# 18.net
KiCad netlist of a schematic drawn in Altium Designer
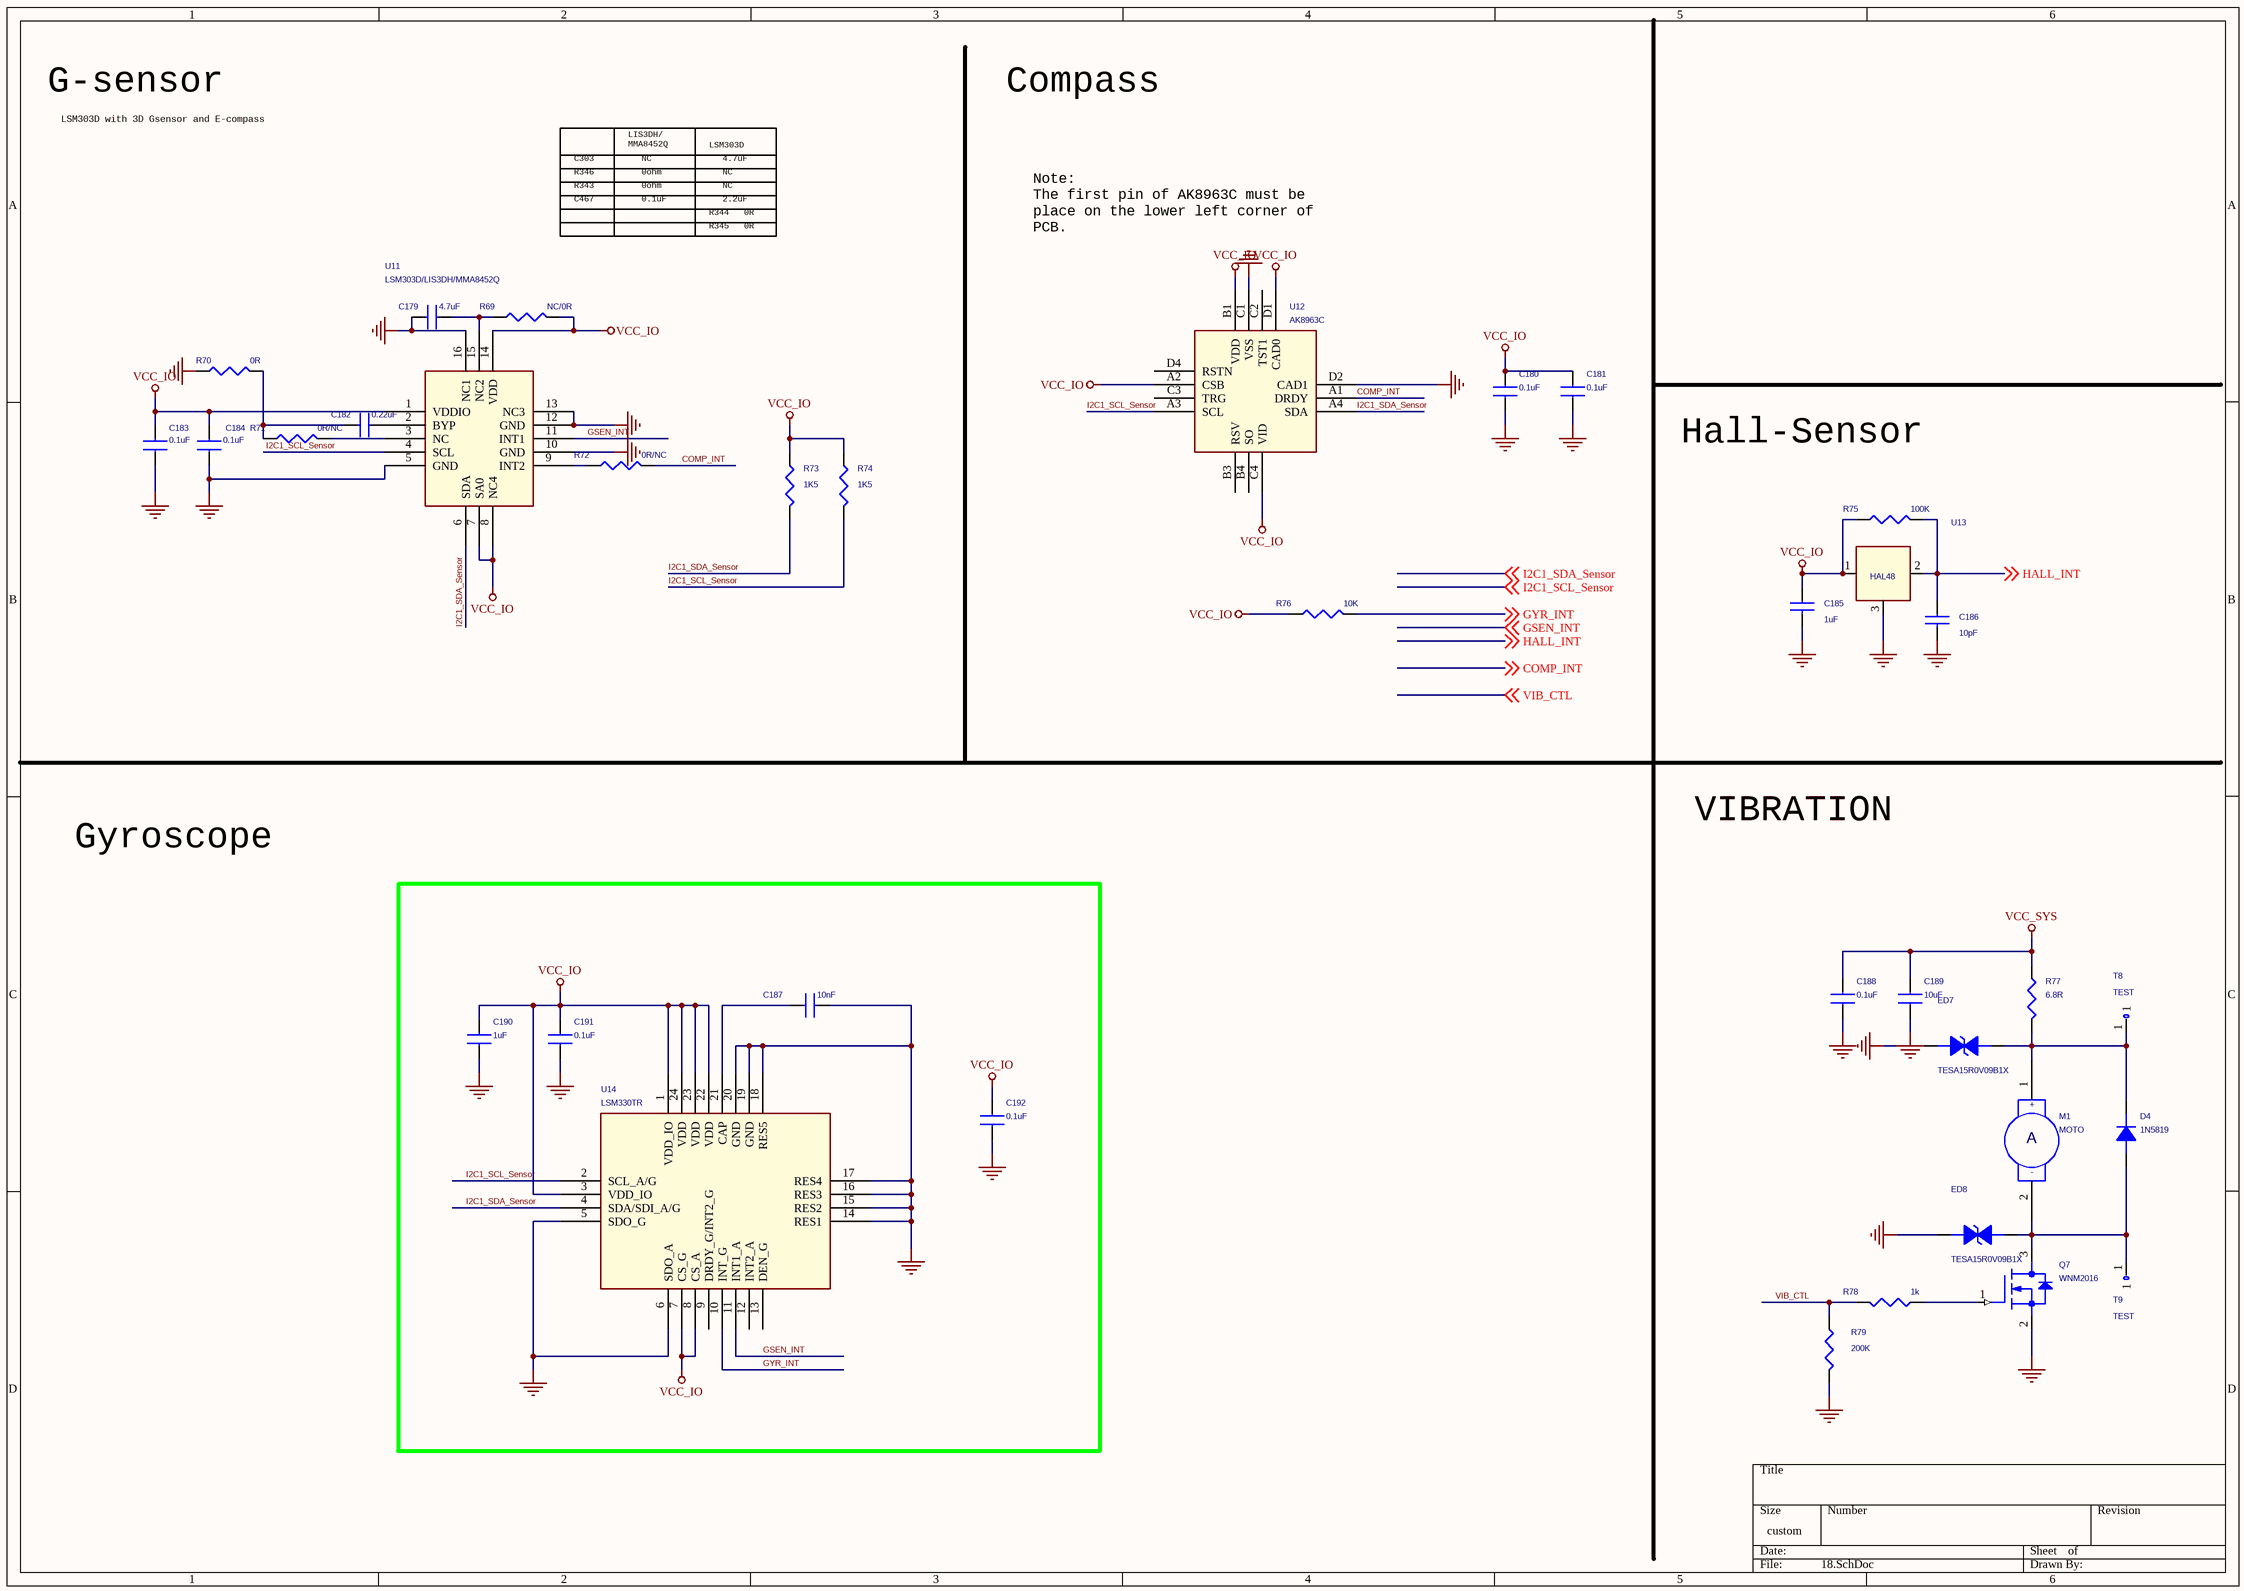
[diagram p0: 18.SchDoc]

(export (version "E")
  (design (tool "Eeschema 10.0.6"))
  (components
    (comp (ref "C179")
      (value "4.7uF")
      (footprint "C0603")
      (description "RoHS CHIP CAP 4.7uF +10/-10% X5R")
      (libsource (lib "*") (part "CAP NP_Dup3"))
    )
    (comp (ref "C180") (value "0.1uF") (footprint "C0603") (libsource (lib "*") (part "CAP NP_Dup3")))
    (comp (ref "C181") (value "0.1uF") (footprint "C0603") (libsource (lib "*") (part "CAP NP_Dup3")))
    (comp (ref "C182")
      (value "0.22uF")
      (footprint "C0603")
      (description "RoHS CHIP CAP 0.22uF +10/-10% X7R")
      (libsource (lib "*") (part "CAP NP_Dup3"))
    )
    (comp (ref "C183")
      (value "0.1uF")
      (footprint "C0603")
      (description "RoHS CHIP CAP 0.1uF +10/-10% X7R")
      (libsource (lib "*") (part "CAP NP_Dup3"))
    )
    (comp (ref "C184")
      (value "0.1uF")
      (footprint "C0603")
      (description "RoHS CHIP CAP 0.1uF +10/-10% X7R")
      (libsource (lib "*") (part "CAP NP_Dup3"))
    )
    (comp (ref "C185")
      (value "1uF")
      (footprint "C0402")
      (description "RoHS CHIP CAP 0.1uF +10/-10% X7R")
      (libsource (lib "*") (part "CAP NP_Dup2"))
    )
    (comp (ref "C186")
      (value "10pF")
      (footprint "C0402")
      (description "RoHS CHIP CAP 0.1uF +10/-10% X7R")
      (libsource (lib "*") (part "CAP NP_Dup2"))
    )
    (comp (ref "C187")
      (value "10nF")
      (footprint "C0603")
      (description "CAP,MLCC,100nF,+/-10%,X7R,6.3V,SMD0402")
      (libsource (lib "*") (part "CAP NP"))
    )
    (comp (ref "C188")
      (value "0.1uF")
      (footprint "C0603")
      (description "CAP,MLCC,100nF,+/-10%,X7R,6.3V,SMD0402")
      (libsource (lib "*") (part "CAP NP_Dup3"))
    )
    (comp (ref "C189")
      (value "10uF")
      (footprint "C0603")
      (description "CAP,MLCC,10uF,+/-10%,X5R,6.3V,SMD0805")
      (libsource (lib "*") (part "CAP NP_Dup3"))
    )
    (comp (ref "C190")
      (value "1uF")
      (footprint "C0603")
      (description "CAP,MLCC,10uF,+/-10%,X5R,6.3V,SMD0805")
      (libsource (lib "*") (part "CAP NP"))
    )
    (comp (ref "C191")
      (value "0.1uF")
      (footprint "C0603")
      (description "CAP,MLCC,100nF,+/-10%,X7R,6.3V,SMD0402")
      (libsource (lib "*") (part "CAP NP"))
    )
    (comp (ref "C192")
      (value "0.1uF")
      (footprint "C0603")
      (description "CAP,MLCC,100nF,+/-10%,X7R,6.3V,SMD0402")
      (libsource (lib "*") (part "CAP NP"))
    )
    (comp (ref "D4")
      (value "1N5819")
      (footprint "SOD323")
      (description "Diode,Schottky,1N5819HW,40V,1A,SOD-123")
      (libsource (lib "*") (part "DIODE_Dup2"))
    )
    (comp (ref "ED7")
      (value "TESA15R0V09B1X")
      (footprint "E0402N")
      (description "ESD Component,5V,30P,SMD,0402")
      (libsource (lib "*") (part "TVS"))
    )
    (comp (ref "ED8")
      (value "TESA15R0V09B1X")
      (footprint "E0402N")
      (description "ESD Component,5V,30P,SMD,0402")
      (libsource (lib "*") (part "TVS"))
    )
    (comp (ref "M1")
      (value "MOTO")
      (footprint "R1206")
      (description "Vibration,R1206,SMT")
      (libsource (lib "*") (part "MOTOR SERVO"))
    )
    (comp (ref "Q7") (value "WNM2016") (footprint "SOT23") (libsource (lib "*") (part "FET N MOS")))
    (comp (ref "R69")
      (value "NC/0R")
      (footprint "R0402")
      (description "NC/ROHS CHIP RES 0R 1/16W +/-5%")
      (libsource (lib "*") (part "RESISTOR_Dup1"))
    )
    (comp (ref "R70")
      (value "0R")
      (footprint "R0402")
      (description "ROHS CHIP RES 0 Ohm 1/16W +/-5%")
      (libsource (lib "*") (part "RESISTOR_Dup1"))
    )
    (comp (ref "R71")
      (value "0R/NC")
      (footprint "R0402")
      (description "NC/ROHS CHIP RES 0R 1/16W +/-5%")
      (libsource (lib "*") (part "RESISTOR_Dup1"))
    )
    (comp (ref "R72")
      (value "0R/NC")
      (footprint "R0402")
      (description "NC/ROHS CHIP RES 0R 1/16W +/-5%")
      (libsource (lib "*") (part "RESISTOR_Dup1"))
    )
    (comp (ref "R73") (value "1K5") (footprint "r0402") (libsource (lib "*") (part "RESISTOR_0_Dup3")))
    (comp (ref "R74") (value "1K5") (footprint "r0402") (libsource (lib "*") (part "RESISTOR_0_Dup3")))
    (comp (ref "R75")
      (value "100K")
      (footprint "R0402")
      (description "ROHS CHIP RES 10K 1/16W 1%")
      (libsource (lib "*") (part "RESISTOR_Dup1"))
    )
    (comp (ref "R76") (value "10K") (footprint "r0402") (libsource (lib "*") (part "RES 1B")))
    (comp (ref "R77")
      (value "6.8R")
      (footprint "R0603")
      (description "RES,thick film,43Ohm,+/-1%,1/8W,SMD0805")
      (libsource (lib "*") (part "RESISTOR_0"))
    )
    (comp (ref "R78")
      (value "1k")
      (footprint "r0402")
      (description "RES,thick film,47KOhm,+/-5%,1/16W,SMD0402")
      (libsource (lib "*") (part "RESISTOR_0_Dup3"))
    )
    (comp (ref "R79")
      (value "200K")
      (footprint "r0402")
      (description "RES,thick film,47KOhm,+/-5%,1/16W,SMD0402")
      (libsource (lib "*") (part "RESISTOR_0_Dup3"))
    )
    (comp (ref "T8") (value "TEST") (footprint "TEST") (libsource (lib "*") (part "TEST_0")))
    (comp (ref "T9") (value "TEST") (footprint "TEST") (libsource (lib "*") (part "TEST_0")))
    (comp (ref "U11")
      (value "LSM303D/LIS3DH/MMA8452Q")
      (footprint "QFN16_COL")
      (description "G_Sensor,LIS3DH/MMA8452Q,1.95V~3.6V,LGA-16,3X3X1.0,-40°C ~ +85°C")
      (libsource (lib "*") (part "MMA8452Q_0"))
    )
    (comp (ref "U12")
      (value "AK8963C")
      (footprint "AK8975B")
      (description "3-axis Electronic Compoass,AK8963C,2.4V~3.6V,BGA14,-40°C~ +85  °C")
      (libsource (lib "*") (part "AK8975C_0"))
    )
    (comp (ref "U13")
      (value "HAL48")
      (footprint "SOT23")
      (description "Trans NPN,SS8050,25V,1500mA,10~60@Vce=1V,Ic=500mA, SOT-23")
      (libsource (lib "*") (part "NPN_0"))
    )
    (comp (ref "U14") (value "LSM330TR") (footprint "L3G4200D") (libsource (lib "*") (part "LSM330")))
  )
  (nets
    (net (code "1") (name "COMP_INT") (class "Default")
      (node (ref "R72") (pin "2") (pinfunction "2_2") (pintype "passive"))
      (node (ref "U12") (pin "A1") (pinfunction "DRDY_A1") (pintype "passive"))
    )
    (net (code "2") (name "GND") (class "Default")
      (node (ref "C179") (pin "2") (pinfunction "2_2") (pintype "passive"))
      (node (ref "C180") (pin "1") (pinfunction "1_1") (pintype "passive"))
      (node (ref "C181") (pin "1") (pinfunction "1_1") (pintype "passive"))
      (node (ref "C183") (pin "1") (pinfunction "1_1") (pintype "passive"))
      (node (ref "C184") (pin "1") (pinfunction "1_1") (pintype "passive"))
      (node (ref "C185") (pin "2") (pinfunction "2_2") (pintype "passive"))
      (node (ref "C186") (pin "2") (pinfunction "2_2") (pintype "passive"))
      (node (ref "C187") (pin "1") (pinfunction "1_1") (pintype "passive"))
      (node (ref "C188") (pin "1") (pinfunction "1_1") (pintype "passive"))
      (node (ref "C189") (pin "1") (pinfunction "1_1") (pintype "passive"))
      (node (ref "C190") (pin "1") (pinfunction "1_1") (pintype "passive"))
      (node (ref "C191") (pin "1") (pinfunction "1_1") (pintype "passive"))
      (node (ref "C192") (pin "1") (pinfunction "1_1") (pintype "passive"))
      (node (ref "ED7") (pin "1") (pinfunction "1_1") (pintype "passive"))
      (node (ref "ED8") (pin "1") (pinfunction "1_1") (pintype "passive"))
      (node (ref "Q7") (pin "2") (pinfunction "SOURCE_2") (pintype "passive"))
      (node (ref "R70") (pin "1") (pinfunction "1_1") (pintype "passive"))
      (node (ref "R79") (pin "2") (pinfunction "2_2") (pintype "passive"))
      (node (ref "U11") (pin "10") (pinfunction "GND_10") (pintype "power_in"))
      (node (ref "U11") (pin "12") (pinfunction "GND_12") (pintype "power_in"))
      (node (ref "U11") (pin "13") (pinfunction "NC3_13") (pintype "passive"))
      (node (ref "U11") (pin "16") (pinfunction "NC1_16") (pintype "passive"))
      (node (ref "U11") (pin "5") (pinfunction "GND_5") (pintype "power_in"))
      (node (ref "U12") (pin "C1") (pinfunction "VSS_C1") (pintype "passive"))
      (node (ref "U12") (pin "D2") (pinfunction "CAD1_D2") (pintype "passive"))
      (node (ref "U13") (pin "3") (pinfunction "3_3") (pintype "passive"))
      (node (ref "U14") (pin "14") (pinfunction "RES1_14") (pintype "passive"))
      (node (ref "U14") (pin "15") (pinfunction "RES2_15") (pintype "passive"))
      (node (ref "U14") (pin "16") (pinfunction "RES3_16") (pintype "passive"))
      (node (ref "U14") (pin "17") (pinfunction "RES4_17") (pintype "passive"))
      (node (ref "U14") (pin "18") (pinfunction "RES5_18") (pintype "passive"))
      (node (ref "U14") (pin "19") (pinfunction "GND_19") (pintype "power_in"))
      (node (ref "U14") (pin "20") (pinfunction "GND_20") (pintype "power_in"))
      (node (ref "U14") (pin "5") (pinfunction "SDO_G_5") (pintype "passive"))
      (node (ref "U14") (pin "6") (pinfunction "SDO_A_6") (pintype "passive"))
    )
    (net (code "3") (name "GSEN_INT") (class "Default")
      (node (ref "U11") (pin "11") (pinfunction "INT1_11") (pintype "passive"))
      (node (ref "U14") (pin "11") (pinfunction "INT1_A_11") (pintype "passive"))
    )
    (net (code "4") (name "GYR_INT") (class "Default")
      (node (ref "R76") (pin "2") (pinfunction "2_2") (pintype "passive"))
      (node (ref "U14") (pin "10") (pinfunction "INT_G_10") (pintype "passive"))
    )
    (net (code "5") (name "HALL_INT") (class "Default")
      (node (ref "C186") (pin "1") (pinfunction "1_1") (pintype "passive"))
      (node (ref "R75") (pin "2") (pinfunction "2_2") (pintype "passive"))
      (node (ref "U13") (pin "2") (pinfunction "2_2") (pintype "passive"))
    )
    (net (code "6") (name "I2C1_SCL_Sensor") (class "Default")
      (node (ref "R74") (pin "2") (pinfunction "2_2") (pintype "passive"))
      (node (ref "U11") (pin "4") (pinfunction "SCL_4") (pintype "passive"))
      (node (ref "U12") (pin "A3") (pinfunction "SCL_A3") (pintype "passive"))
      (node (ref "U14") (pin "2") (pinfunction "SCL_A/G_2") (pintype "passive"))
    )
    (net (code "7") (name "I2C1_SDA_Sensor") (class "Default")
      (node (ref "R73") (pin "2") (pinfunction "2_2") (pintype "passive"))
      (node (ref "U11") (pin "6") (pinfunction "SDA_6") (pintype "passive"))
      (node (ref "U12") (pin "A4") (pinfunction "SDA_A4") (pintype "passive"))
      (node (ref "U14") (pin "4") (pinfunction "SDA/SDI_A/G_4") (pintype "passive"))
    )
    (net (code "8") (name "Net-(C182-Pad2)") (class "Default")
      (node (ref "C182") (pin "2") (pinfunction "2_2") (pintype "passive"))
      (node (ref "R70") (pin "2") (pinfunction "2_2") (pintype "passive"))
      (node (ref "R71") (pin "1") (pinfunction "1_1") (pintype "passive"))
    )
    (net (code "9") (name "Net-(D4-A)") (class "Default")
      (node (ref "D4") (pin "1") (pinfunction "A_1") (pintype "passive"))
      (node (ref "ED8") (pin "2") (pinfunction "2_2") (pintype "passive"))
      (node (ref "M1") (pin "2") (pinfunction "-_2") (pintype "passive"))
      (node (ref "Q7") (pin "3") (pinfunction "DRAIN_3") (pintype "passive"))
      (node (ref "T9") (pin "1") (pinfunction "1_1") (pintype "passive"))
    )
    (net (code "10") (name "Net-(D4-K)") (class "Default")
      (node (ref "D4") (pin "2") (pinfunction "K_2") (pintype "passive"))
      (node (ref "ED7") (pin "2") (pinfunction "2_2") (pintype "passive"))
      (node (ref "M1") (pin "1") (pinfunction "+_1") (pintype "passive"))
      (node (ref "R77") (pin "2") (pinfunction "2_2") (pintype "passive"))
      (node (ref "T8") (pin "1") (pinfunction "1_1") (pintype "passive"))
    )
    (net (code "11") (name "Net-(Q7-GATE)") (class "Default")
      (node (ref "Q7") (pin "1") (pinfunction "GATE_1") (pintype "input"))
      (node (ref "R78") (pin "1") (pinfunction "1_1") (pintype "passive"))
    )
    (net (code "12") (name "Net-(U11-BYP)") (class "Default")
      (node (ref "C182") (pin "1") (pinfunction "1_1") (pintype "passive"))
      (node (ref "U11") (pin "2") (pinfunction "BYP_2") (pintype "passive"))
    )
    (net (code "13") (name "Net-(U11-INT2)") (class "Default")
      (node (ref "R72") (pin "1") (pinfunction "1_1") (pintype "passive"))
      (node (ref "U11") (pin "9") (pinfunction "INT2_9") (pintype "passive"))
    )
    (net (code "14") (name "Net-(U11-NC)") (class "Default")
      (node (ref "R71") (pin "2") (pinfunction "2_2") (pintype "passive"))
      (node (ref "U11") (pin "3") (pinfunction "NC_3") (pintype "passive"))
    )
    (net (code "15") (name "Net-(U11-NC2)") (class "Default")
      (node (ref "C179") (pin "1") (pinfunction "1_1") (pintype "passive"))
      (node (ref "R69") (pin "1") (pinfunction "1_1") (pintype "passive"))
      (node (ref "U11") (pin "15") (pinfunction "NC2_15") (pintype "passive"))
    )
    (net (code "16") (name "Net-(U14-CAP)") (class "Default")
      (node (ref "C187") (pin "2") (pinfunction "2_2") (pintype "passive"))
      (node (ref "U14") (pin "21") (pinfunction "CAP_21") (pintype "passive"))
    )
    (net (code "17") (name "VCC_IO") (class "Default")
      (node (ref "C180") (pin "2") (pinfunction "2_2") (pintype "passive"))
      (node (ref "C181") (pin "2") (pinfunction "2_2") (pintype "passive"))
      (node (ref "C183") (pin "2") (pinfunction "2_2") (pintype "passive"))
      (node (ref "C184") (pin "2") (pinfunction "2_2") (pintype "passive"))
      (node (ref "C185") (pin "1") (pinfunction "1_1") (pintype "passive"))
      (node (ref "C190") (pin "2") (pinfunction "2_2") (pintype "passive"))
      (node (ref "C191") (pin "2") (pinfunction "2_2") (pintype "passive"))
      (node (ref "C192") (pin "2") (pinfunction "2_2") (pintype "passive"))
      (node (ref "R69") (pin "2") (pinfunction "2_2") (pintype "passive"))
      (node (ref "R73") (pin "1") (pinfunction "1_1") (pintype "passive"))
      (node (ref "R74") (pin "1") (pinfunction "1_1") (pintype "passive"))
      (node (ref "R75") (pin "1") (pinfunction "1_1") (pintype "passive"))
      (node (ref "R76") (pin "1") (pinfunction "1_1") (pintype "passive"))
      (node (ref "U11") (pin "1") (pinfunction "VDDIO_1") (pintype "passive"))
      (node (ref "U11") (pin "14") (pinfunction "VDD_14") (pintype "passive"))
      (node (ref "U11") (pin "7") (pinfunction "SA0_7") (pintype "passive"))
      (node (ref "U11") (pin "8") (pinfunction "NC4_8") (pintype "passive"))
      (node (ref "U12") (pin "A2") (pinfunction "CSB_A2") (pintype "passive"))
      (node (ref "U12") (pin "B1") (pinfunction "VDD_B1") (pintype "passive"))
      (node (ref "U12") (pin "C4") (pinfunction "VID_C4") (pintype "passive"))
      (node (ref "U12") (pin "D1") (pinfunction "CAD0_D1") (pintype "passive"))
      (node (ref "U13") (pin "1") (pinfunction "1_1") (pintype "passive"))
      (node (ref "U14") (pin "1") (pinfunction "VDD_IO_1") (pintype "power_in"))
      (node (ref "U14") (pin "22") (pinfunction "VDD_22") (pintype "power_in"))
      (node (ref "U14") (pin "23") (pinfunction "VDD_23") (pintype "power_in"))
      (node (ref "U14") (pin "24") (pinfunction "VDD_24") (pintype "power_in"))
      (node (ref "U14") (pin "3") (pinfunction "VDD_IO_3") (pintype "power_in"))
      (node (ref "U14") (pin "7") (pinfunction "CS_G_7") (pintype "passive"))
      (node (ref "U14") (pin "8") (pinfunction "CS_A_8") (pintype "passive"))
    )
    (net (code "18") (name "VCC_SYS") (class "Default")
      (node (ref "C188") (pin "2") (pinfunction "2_2") (pintype "passive"))
      (node (ref "C189") (pin "2") (pinfunction "2_2") (pintype "passive"))
      (node (ref "R77") (pin "1") (pinfunction "1_1") (pintype "passive"))
    )
    (net (code "19") (name "VIB_CTL") (class "Default")
      (node (ref "R78") (pin "2") (pinfunction "2_2") (pintype "passive"))
      (node (ref "R79") (pin "1") (pinfunction "1_1") (pintype "passive"))
    )
    (net (code "20") (name "unconnected-(U12-RSTN-PadD4)") (class "Default")
      (node (ref "U12") (pin "D4") (pinfunction "RSTN_D4") (pintype "passive"))
    )
    (net (code "21") (name "unconnected-(U12-RSV-PadB3)") (class "Default")
      (node (ref "U12") (pin "B3") (pinfunction "RSV_B3") (pintype "passive"))
    )
    (net (code "22") (name "unconnected-(U12-SO-PadB4)") (class "Default")
      (node (ref "U12") (pin "B4") (pinfunction "SO_B4") (pintype "passive"))
    )
    (net (code "23") (name "unconnected-(U12-TRG-PadC3)") (class "Default")
      (node (ref "U12") (pin "C3") (pinfunction "TRG_C3") (pintype "passive"))
    )
    (net (code "24") (name "unconnected-(U12-TST1-PadC2)") (class "Default")
      (node (ref "U12") (pin "C2") (pinfunction "TST1_C2") (pintype "passive"))
    )
    (net (code "25") (name "unconnected-(U14-DEN_G-Pad13)") (class "Default")
      (node (ref "U14") (pin "13") (pinfunction "DEN_G_13") (pintype "passive"))
    )
    (net (code "26") (name "unconnected-(U14-DRDY_G{slash}INT2_G-Pad9)") (class "Default")
      (node (ref "U14") (pin "9") (pinfunction "DRDY_G/INT2_G_9") (pintype "passive"))
    )
    (net (code "27") (name "unconnected-(U14-INT2_A-Pad12)") (class "Default")
      (node (ref "U14") (pin "12") (pinfunction "INT2_A_12") (pintype "passive"))
    )
  )
)
